# OpenLCD.net
KiCad netlist of a schematic drawn in EAGLE
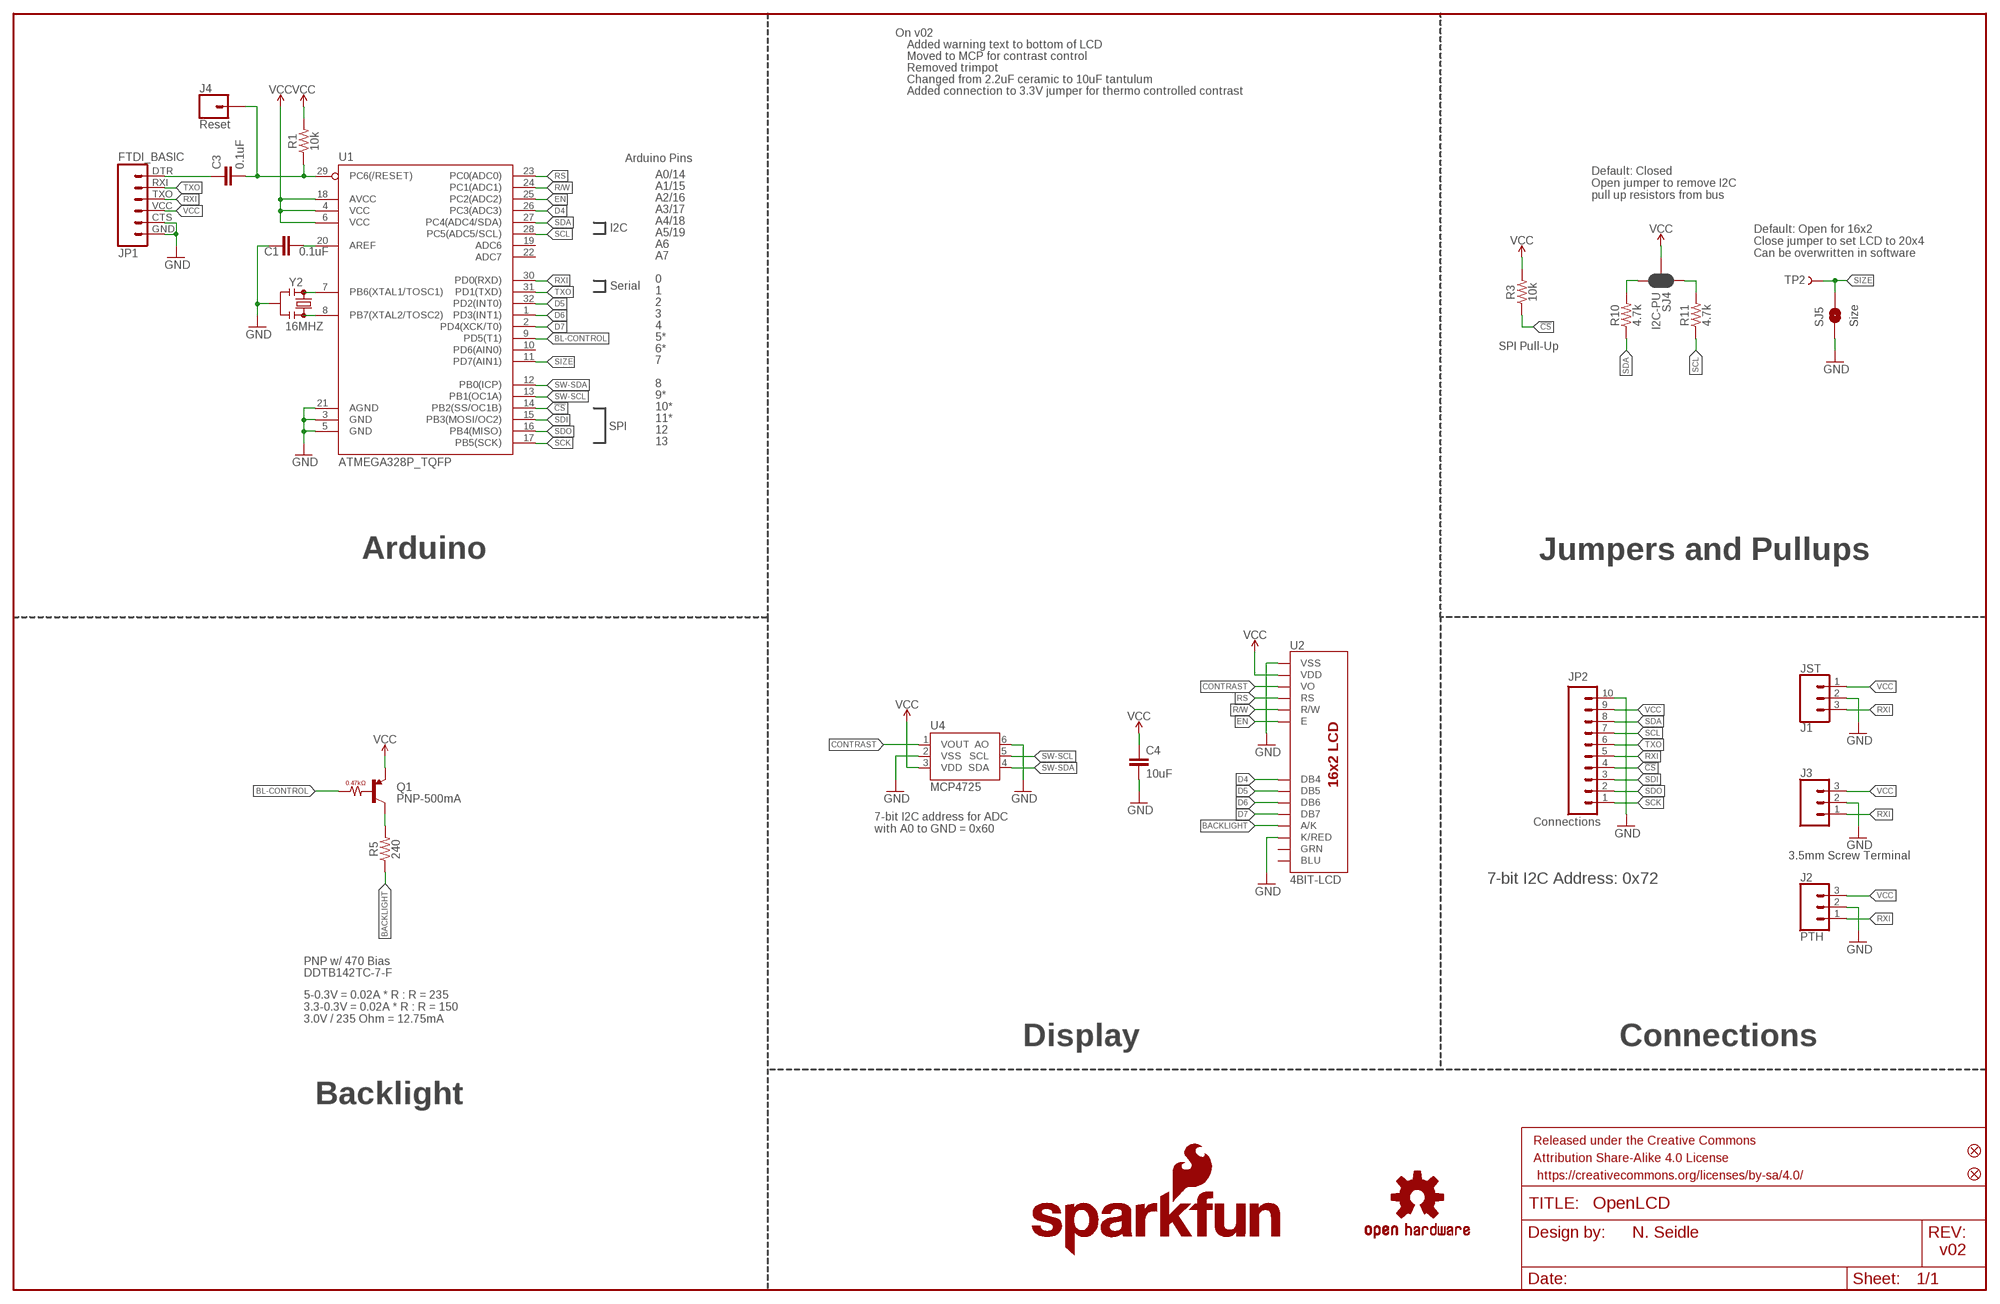
[diagram p0: schematic, sheet 1]

(export (version "E")
  (design (tool "Eeschema 10.0.6"))
  (components
    (comp (ref "C1")
      (value "0.1uF")
      (footprint "eagle-import:0603")
      (libsource (lib "eagle-import") (part "0.1UF-0603-25V-(+80/-20%)"))
    )
    (comp (ref "C3")
      (value "0.1uF")
      (footprint "eagle-import:0603")
      (libsource (lib "eagle-import") (part "0.1UF-0603-25V-(+80/-20%)"))
    )
    (comp (ref "C4")
      (value "10uF")
      (footprint "eagle-import:0805")
      (libsource (lib "eagle-import") (part "10UF-0805-10V-10%"))
    )
    (comp (ref "FID1")
      (value "FIDUCIAL1X2")
      (footprint "eagle-import:FIDUCIAL-1X2")
      (libsource (lib "eagle-import") (part "FIDUCIAL1X2"))
    )
    (comp (ref "FID2")
      (value "FIDUCIAL1X2")
      (footprint "eagle-import:FIDUCIAL-1X2")
      (libsource (lib "eagle-import") (part "FIDUCIAL1X2"))
    )
    (comp (ref "FRAME1")
      (value "FRAME-LEDGER")
      (footprint "eagle-import:CREATIVE_COMMONS")
      (fields (field (name "DESIGNER") "N. Seidle") (field (name "VERSION") "01"))
      (libsource (lib "eagle-import") (part "FRAME-LEDGER"))
    )
    (comp (ref "J1")
      (value "JST")
      (footprint "eagle-import:JST-3-PTH")
      (libsource (lib "eagle-import") (part "CONN_03JST-PTH"))
    )
    (comp (ref "J2")
      (value "PTH")
      (footprint "eagle-import:1X03")
      (libsource (lib "eagle-import") (part "CONN_03"))
    )
    (comp (ref "J3")
      (value "3.5mm Screw Terminal")
      (footprint "eagle-import:SCREWTERMINAL-3.5MM-3_LOCK.007S")
      (libsource (lib "eagle-import") (part "CONN_03SCREW_LOCK"))
    )
    (comp (ref "J4")
      (value "Reset")
      (footprint "eagle-import:1X01_NO_SILK")
      (libsource (lib "eagle-import") (part "CONN_01PTH_NO_SILK_YES_STOP"))
    )
    (comp (ref "JP1")
      (value "FTDI_BASIC")
      (footprint "eagle-import:FTDI_BASIC")
      (libsource (lib "eagle-import") (part "FTDI_BASICPTH"))
    )
    (comp (ref "JP2")
      (value "Connections")
      (footprint "eagle-import:1X10")
      (libsource (lib "eagle-import") (part "CONN_10{dblquote}"))
    )
    (comp (ref "LOGO3")
      (value "SFE_LOGO_NAME.1_INCH")
      (footprint "eagle-import:SFE_LOGO_NAME_.1")
      (libsource (lib "eagle-import") (part "SFE_LOGO_NAME.1_INCH"))
    )
    (comp (ref "LOGO4")
      (value "SFE_LOGO_FLAME.1_STOP")
      (footprint "eagle-import:SFE_LOGO_FLAME_STOP_.1")
      (libsource (lib "eagle-import") (part "SFE_LOGO_FLAME.1_STOP"))
    )
    (comp (ref "Q1")
      (value "PNP-500mA")
      (footprint "eagle-import:SOT23-3")
      (libsource (lib "eagle-import") (part "TRANSISTOR-PNP-DDTB142TC"))
    )
    (comp (ref "R1")
      (value "10k")
      (footprint "eagle-import:0603")
      (libsource (lib "eagle-import") (part "10KOHM-0603-1/10W-1%"))
    )
    (comp (ref "R3")
      (value "10k")
      (footprint "eagle-import:0603")
      (libsource (lib "eagle-import") (part "10KOHM-0603-1/10W-1%"))
    )
    (comp (ref "R5")
      (value "240")
      (footprint "eagle-import:0603")
      (libsource (lib "eagle-import") (part "240OHM-0603-1/10W-1%"))
    )
    (comp (ref "R10")
      (value "4.7k")
      (footprint "eagle-import:0603")
      (libsource (lib "eagle-import") (part "4.7KOHM-0603-1/10W-1%"))
    )
    (comp (ref "R11")
      (value "4.7k")
      (footprint "eagle-import:0603")
      (libsource (lib "eagle-import") (part "4.7KOHM-0603-1/10W-1%"))
    )
    (comp (ref "SJ4")
      (value "I2C-PU")
      (footprint "eagle-import:PAD-JUMPER-3-NC_BY_PASTE_YES_SILK_FULL_BOX")
      (libsource (lib "eagle-import") (part "JUMPER-PAD-3-NC_BY_PASTE"))
    )
    (comp (ref "SJ5")
      (value "Size")
      (footprint "eagle-import:PAD-JUMPER-2-NO_YES_SILK")
      (libsource (lib "eagle-import") (part "JUMPER-PAD-2-NOYES_SILK"))
    )
    (comp (ref "TP2")
      (value "TEST-POINT3X4")
      (footprint "eagle-import:PAD.03X.04")
      (libsource (lib "eagle-import") (part "TEST-POINT3X4"))
    )
    (comp (ref "U$4")
      (value "OSHW-LOGOS")
      (footprint "eagle-import:OSHW-LOGO-S")
      (libsource (lib "eagle-import") (part "OSHW-LOGOS"))
    )
    (comp (ref "U1")
      (value "ATMEGA328P_TQFP")
      (footprint "eagle-import:TQFP32-08")
      (libsource (lib "eagle-import") (part "ATMEGA328P_TQFP"))
    )
    (comp (ref "U2")
      (value "4BIT-LCD")
      (footprint "eagle-import:LCD-16X2_NOSILK-KIT-4BIT")
      (libsource (lib "eagle-import") (part "LCD-16X2-MINMIN4-RGB"))
    )
    (comp (ref "U4")
      (value "MCP4725")
      (footprint "eagle-import:SOT23-6")
      (libsource (lib "eagle-import") (part "MCP4725SOT-23"))
    )
    (comp (ref "Y2")
      (value "16MHZ")
      (footprint "eagle-import:RESONATOR-SMD")
      (libsource (lib "eagle-import") (part "RESONATOR8MHZ"))
    )
  )
  (nets
    (net (code "1") (name "/BLU") (class "Default")
      (node (ref "U2") (pin "18") (pinfunction "BLU_18") (pintype "power_in"))
    )
    (net (code "2") (name "/GRN") (class "Default")
      (node (ref "U2") (pin "17") (pinfunction "GRN_17") (pintype "power_in"))
    )
    (net (code "3") (name "/~{CS}") (class "Default")
      (node (ref "JP2") (pin "4") (pinfunction "4_4") (pintype "passive"))
      (node (ref "R3") (pin "1") (pinfunction "1_1") (pintype "passive"))
      (node (ref "U1") (pin "14") (pinfunction "PB2(SS/OC1B)_14") (pintype "bidirectional"))
    )
    (net (code "4") (name "BACKLIGHT") (class "Default")
      (node (ref "R5") (pin "1") (pinfunction "1_1") (pintype "passive"))
      (node (ref "U2") (pin "15") (pinfunction "A/K_15") (pintype "power_in"))
    )
    (net (code "5") (name "BL-CONTROL") (class "Default")
      (node (ref "Q1") (pin "1") (pinfunction "B_1") (pintype "passive"))
      (node (ref "U1") (pin "9") (pinfunction "PD5(T1)_9") (pintype "bidirectional"))
    )
    (net (code "6") (name "CONTRAST") (class "Default")
      (node (ref "U2") (pin "3") (pinfunction "VO_3") (pintype "bidirectional"))
      (node (ref "U4") (pin "1") (pinfunction "VOUT_1") (pintype "bidirectional"))
    )
    (net (code "7") (name "D4") (class "Default")
      (node (ref "U1") (pin "26") (pinfunction "PC3(ADC3)_26") (pintype "bidirectional"))
      (node (ref "U2") (pin "11") (pinfunction "DB4_11") (pintype "bidirectional"))
    )
    (net (code "8") (name "D5") (class "Default")
      (node (ref "U1") (pin "32") (pinfunction "PD2(INT0)_32") (pintype "bidirectional"))
      (node (ref "U2") (pin "12") (pinfunction "DB5_12") (pintype "bidirectional"))
    )
    (net (code "9") (name "D6") (class "Default")
      (node (ref "U1") (pin "1") (pinfunction "PD3(INT1)_1") (pintype "bidirectional"))
      (node (ref "U2") (pin "13") (pinfunction "DB6_13") (pintype "bidirectional"))
    )
    (net (code "10") (name "D7") (class "Default")
      (node (ref "U1") (pin "2") (pinfunction "PD4(XCK/T0)_2") (pintype "bidirectional"))
      (node (ref "U2") (pin "14") (pinfunction "DB7_14") (pintype "bidirectional"))
    )
    (net (code "11") (name "EN") (class "Default")
      (node (ref "U1") (pin "25") (pinfunction "PC2(ADC2)_25") (pintype "bidirectional"))
      (node (ref "U2") (pin "6") (pinfunction "E_6") (pintype "input"))
    )
    (net (code "12") (name "GND") (class "Default")
      (node (ref "C1") (pin "1") (pinfunction "1_1") (pintype "passive"))
      (node (ref "C4") (pin "2") (pinfunction "2_2") (pintype "passive"))
      (node (ref "J1") (pin "2") (pinfunction "2_2") (pintype "passive"))
      (node (ref "J2") (pin "2") (pinfunction "2_2") (pintype "passive"))
      (node (ref "J3") (pin "2") (pinfunction "2_2") (pintype "passive"))
      (node (ref "JP1") (pin "CTS") (pinfunction "5_CTS") (pintype "passive"))
      (node (ref "JP1") (pin "GND") (pinfunction "6_GND") (pintype "passive"))
      (node (ref "JP2") (pin "10") (pinfunction "10_10") (pintype "passive"))
      (node (ref "SJ5") (pin "1") (pinfunction "1_1") (pintype "passive"))
      (node (ref "U1") (pin "21") (pinfunction "AGND_21") (pintype "bidirectional"))
      (node (ref "U1") (pin "3") (pinfunction "GND_3") (pintype "bidirectional"))
      (node (ref "U1") (pin "5") (pinfunction "GND_5") (pintype "bidirectional"))
      (node (ref "U2") (pin "1") (pinfunction "VSS_1") (pintype "power_in"))
      (node (ref "U2") (pin "16") (pinfunction "K/RED_16") (pintype "power_in"))
      (node (ref "U4") (pin "2") (pinfunction "VSS_2") (pintype "bidirectional"))
      (node (ref "U4") (pin "6") (pinfunction "AO_6") (pintype "bidirectional"))
      (node (ref "Y2") (pin "2") (pinfunction "2_2") (pintype "passive"))
    )
    (net (code "13") (name "Net-(JP1-1)") (class "Default")
      (node (ref "C3") (pin "1") (pinfunction "1_1") (pintype "passive"))
      (node (ref "JP1") (pin "DTR") (pinfunction "1_DTR") (pintype "passive"))
    )
    (net (code "14") (name "Net-(Q1-C)") (class "Default")
      (node (ref "Q1") (pin "3") (pinfunction "C_3") (pintype "passive"))
      (node (ref "R5") (pin "2") (pinfunction "2_2") (pintype "passive"))
    )
    (net (code "15") (name "Net-(R10-Pad2)") (class "Default")
      (node (ref "R10") (pin "2") (pinfunction "2_2") (pintype "passive"))
      (node (ref "SJ4") (pin "3") (pinfunction "3_3") (pintype "passive"))
    )
    (net (code "16") (name "Net-(R11-Pad2)") (class "Default")
      (node (ref "R11") (pin "2") (pinfunction "2_2") (pintype "passive"))
      (node (ref "SJ4") (pin "1") (pinfunction "1_1") (pintype "passive"))
    )
    (net (code "17") (name "Net-(U1-AREF)") (class "Default")
      (node (ref "C1") (pin "2") (pinfunction "2_2") (pintype "passive"))
      (node (ref "U1") (pin "20") (pinfunction "AREF_20") (pintype "bidirectional"))
    )
    (net (code "18") (name "Net-(U1-PB6(XTAL1{slash}TOSC1))") (class "Default")
      (node (ref "U1") (pin "7") (pinfunction "PB6(XTAL1/TOSC1)_7") (pintype "bidirectional"))
      (node (ref "Y2") (pin "1") (pinfunction "1_1") (pintype "passive"))
    )
    (net (code "19") (name "Net-(U1-PB7(XTAL2{slash}TOSC2))") (class "Default")
      (node (ref "U1") (pin "8") (pinfunction "PB7(XTAL2/TOSC2)_8") (pintype "bidirectional"))
      (node (ref "Y2") (pin "3") (pinfunction "3_3") (pintype "passive"))
    )
    (net (code "20") (name "Net-(U1-PC6({slash}RESET))") (class "Default")
      (node (ref "C3") (pin "2") (pinfunction "2_2") (pintype "passive"))
      (node (ref "J4") (pin "1") (pinfunction "1_1") (pintype "passive"))
      (node (ref "R1") (pin "1") (pinfunction "1_1") (pintype "passive"))
      (node (ref "U1") (pin "29") (pinfunction "PC6(/RESET)_29") (pintype "bidirectional"))
    )
    (net (code "21") (name "RS") (class "Default")
      (node (ref "U1") (pin "23") (pinfunction "PC0(ADC0)_23") (pintype "bidirectional"))
      (node (ref "U2") (pin "4") (pinfunction "RS_4") (pintype "input"))
    )
    (net (code "22") (name "RXI") (class "Default")
      (node (ref "J1") (pin "3") (pinfunction "3_3") (pintype "passive"))
      (node (ref "J2") (pin "1") (pinfunction "1_1") (pintype "passive"))
      (node (ref "J3") (pin "1") (pinfunction "1_1") (pintype "passive"))
      (node (ref "JP1") (pin "TXO") (pinfunction "3_TXO") (pintype "passive"))
      (node (ref "JP2") (pin "5") (pinfunction "5_5") (pintype "passive"))
      (node (ref "U1") (pin "30") (pinfunction "PD0(RXD)_30") (pintype "bidirectional"))
    )
    (net (code "23") (name "R{slash}W") (class "Default")
      (node (ref "U1") (pin "24") (pinfunction "PC1(ADC1)_24") (pintype "bidirectional"))
      (node (ref "U2") (pin "5") (pinfunction "R/W_5") (pintype "input"))
    )
    (net (code "24") (name "SCK") (class "Default")
      (node (ref "JP2") (pin "1") (pinfunction "1_1") (pintype "passive"))
      (node (ref "U1") (pin "17") (pinfunction "PB5(SCK)_17") (pintype "bidirectional"))
    )
    (net (code "25") (name "SCL") (class "Default")
      (node (ref "JP2") (pin "7") (pinfunction "7_7") (pintype "passive"))
      (node (ref "R11") (pin "1") (pinfunction "1_1") (pintype "passive"))
      (node (ref "U1") (pin "28") (pinfunction "PC5(ADC5/SCL)_28") (pintype "bidirectional"))
    )
    (net (code "26") (name "SDA") (class "Default")
      (node (ref "JP2") (pin "8") (pinfunction "8_8") (pintype "passive"))
      (node (ref "R10") (pin "1") (pinfunction "1_1") (pintype "passive"))
      (node (ref "U1") (pin "27") (pinfunction "PC4(ADC4/SDA)_27") (pintype "bidirectional"))
    )
    (net (code "27") (name "SDI") (class "Default")
      (node (ref "JP2") (pin "3") (pinfunction "3_3") (pintype "passive"))
      (node (ref "U1") (pin "15") (pinfunction "PB3(MOSI/OC2)_15") (pintype "bidirectional"))
    )
    (net (code "28") (name "SDO") (class "Default")
      (node (ref "JP2") (pin "2") (pinfunction "2_2") (pintype "passive"))
      (node (ref "U1") (pin "16") (pinfunction "PB4(MISO)_16") (pintype "bidirectional"))
    )
    (net (code "29") (name "SIZE") (class "Default")
      (node (ref "SJ5") (pin "2") (pinfunction "2_2") (pintype "passive"))
      (node (ref "TP2") (pin "P$1") (pinfunction "1_P$1") (pintype "bidirectional"))
      (node (ref "U1") (pin "11") (pinfunction "PD7(AIN1)_11") (pintype "bidirectional"))
    )
    (net (code "30") (name "SW-SCL") (class "Default")
      (node (ref "U1") (pin "13") (pinfunction "PB1(OC1A)_13") (pintype "bidirectional"))
      (node (ref "U4") (pin "5") (pinfunction "SCL_5") (pintype "bidirectional"))
    )
    (net (code "31") (name "SW-SDA") (class "Default")
      (node (ref "U1") (pin "12") (pinfunction "PB0(ICP)_12") (pintype "bidirectional"))
      (node (ref "U4") (pin "4") (pinfunction "SDA_4") (pintype "bidirectional"))
    )
    (net (code "32") (name "TXO") (class "Default")
      (node (ref "JP1") (pin "RXI") (pinfunction "2_RXI") (pintype "passive"))
      (node (ref "JP2") (pin "6") (pinfunction "6_6") (pintype "passive"))
      (node (ref "U1") (pin "31") (pinfunction "PD1(TXD)_31") (pintype "bidirectional"))
    )
    (net (code "33") (name "VCC") (class "Default")
      (node (ref "C4") (pin "1") (pinfunction "1_1") (pintype "passive"))
      (node (ref "J1") (pin "1") (pinfunction "1_1") (pintype "passive"))
      (node (ref "J2") (pin "3") (pinfunction "3_3") (pintype "passive"))
      (node (ref "J3") (pin "3") (pinfunction "3_3") (pintype "passive"))
      (node (ref "JP1") (pin "VCC") (pinfunction "4_VCC") (pintype "passive"))
      (node (ref "JP2") (pin "9") (pinfunction "9_9") (pintype "passive"))
      (node (ref "Q1") (pin "2") (pinfunction "E_2") (pintype "passive"))
      (node (ref "R1") (pin "2") (pinfunction "2_2") (pintype "passive"))
      (node (ref "R3") (pin "2") (pinfunction "2_2") (pintype "passive"))
      (node (ref "SJ4") (pin "2") (pinfunction "2_2") (pintype "passive"))
      (node (ref "U1") (pin "18") (pinfunction "AVCC_18") (pintype "bidirectional"))
      (node (ref "U1") (pin "4") (pinfunction "VCC_4") (pintype "bidirectional"))
      (node (ref "U1") (pin "6") (pinfunction "VCC_6") (pintype "bidirectional"))
      (node (ref "U2") (pin "2") (pinfunction "VDD_2") (pintype "power_in"))
      (node (ref "U4") (pin "3") (pinfunction "VDD_3") (pintype "bidirectional"))
    )
    (net (code "34") (name "unconnected-(U1-ADC6-Pad19)") (class "Default")
      (node (ref "U1") (pin "19") (pinfunction "ADC6_19") (pintype "bidirectional"))
    )
    (net (code "35") (name "unconnected-(U1-ADC7-Pad22)") (class "Default")
      (node (ref "U1") (pin "22") (pinfunction "ADC7_22") (pintype "bidirectional"))
    )
    (net (code "36") (name "unconnected-(U1-PD6(AIN0)-Pad10)") (class "Default")
      (node (ref "U1") (pin "10") (pinfunction "PD6(AIN0)_10") (pintype "bidirectional"))
    )
  )
)
